# design.net
KiCad netlist of a schematic drawn in Altium Designer
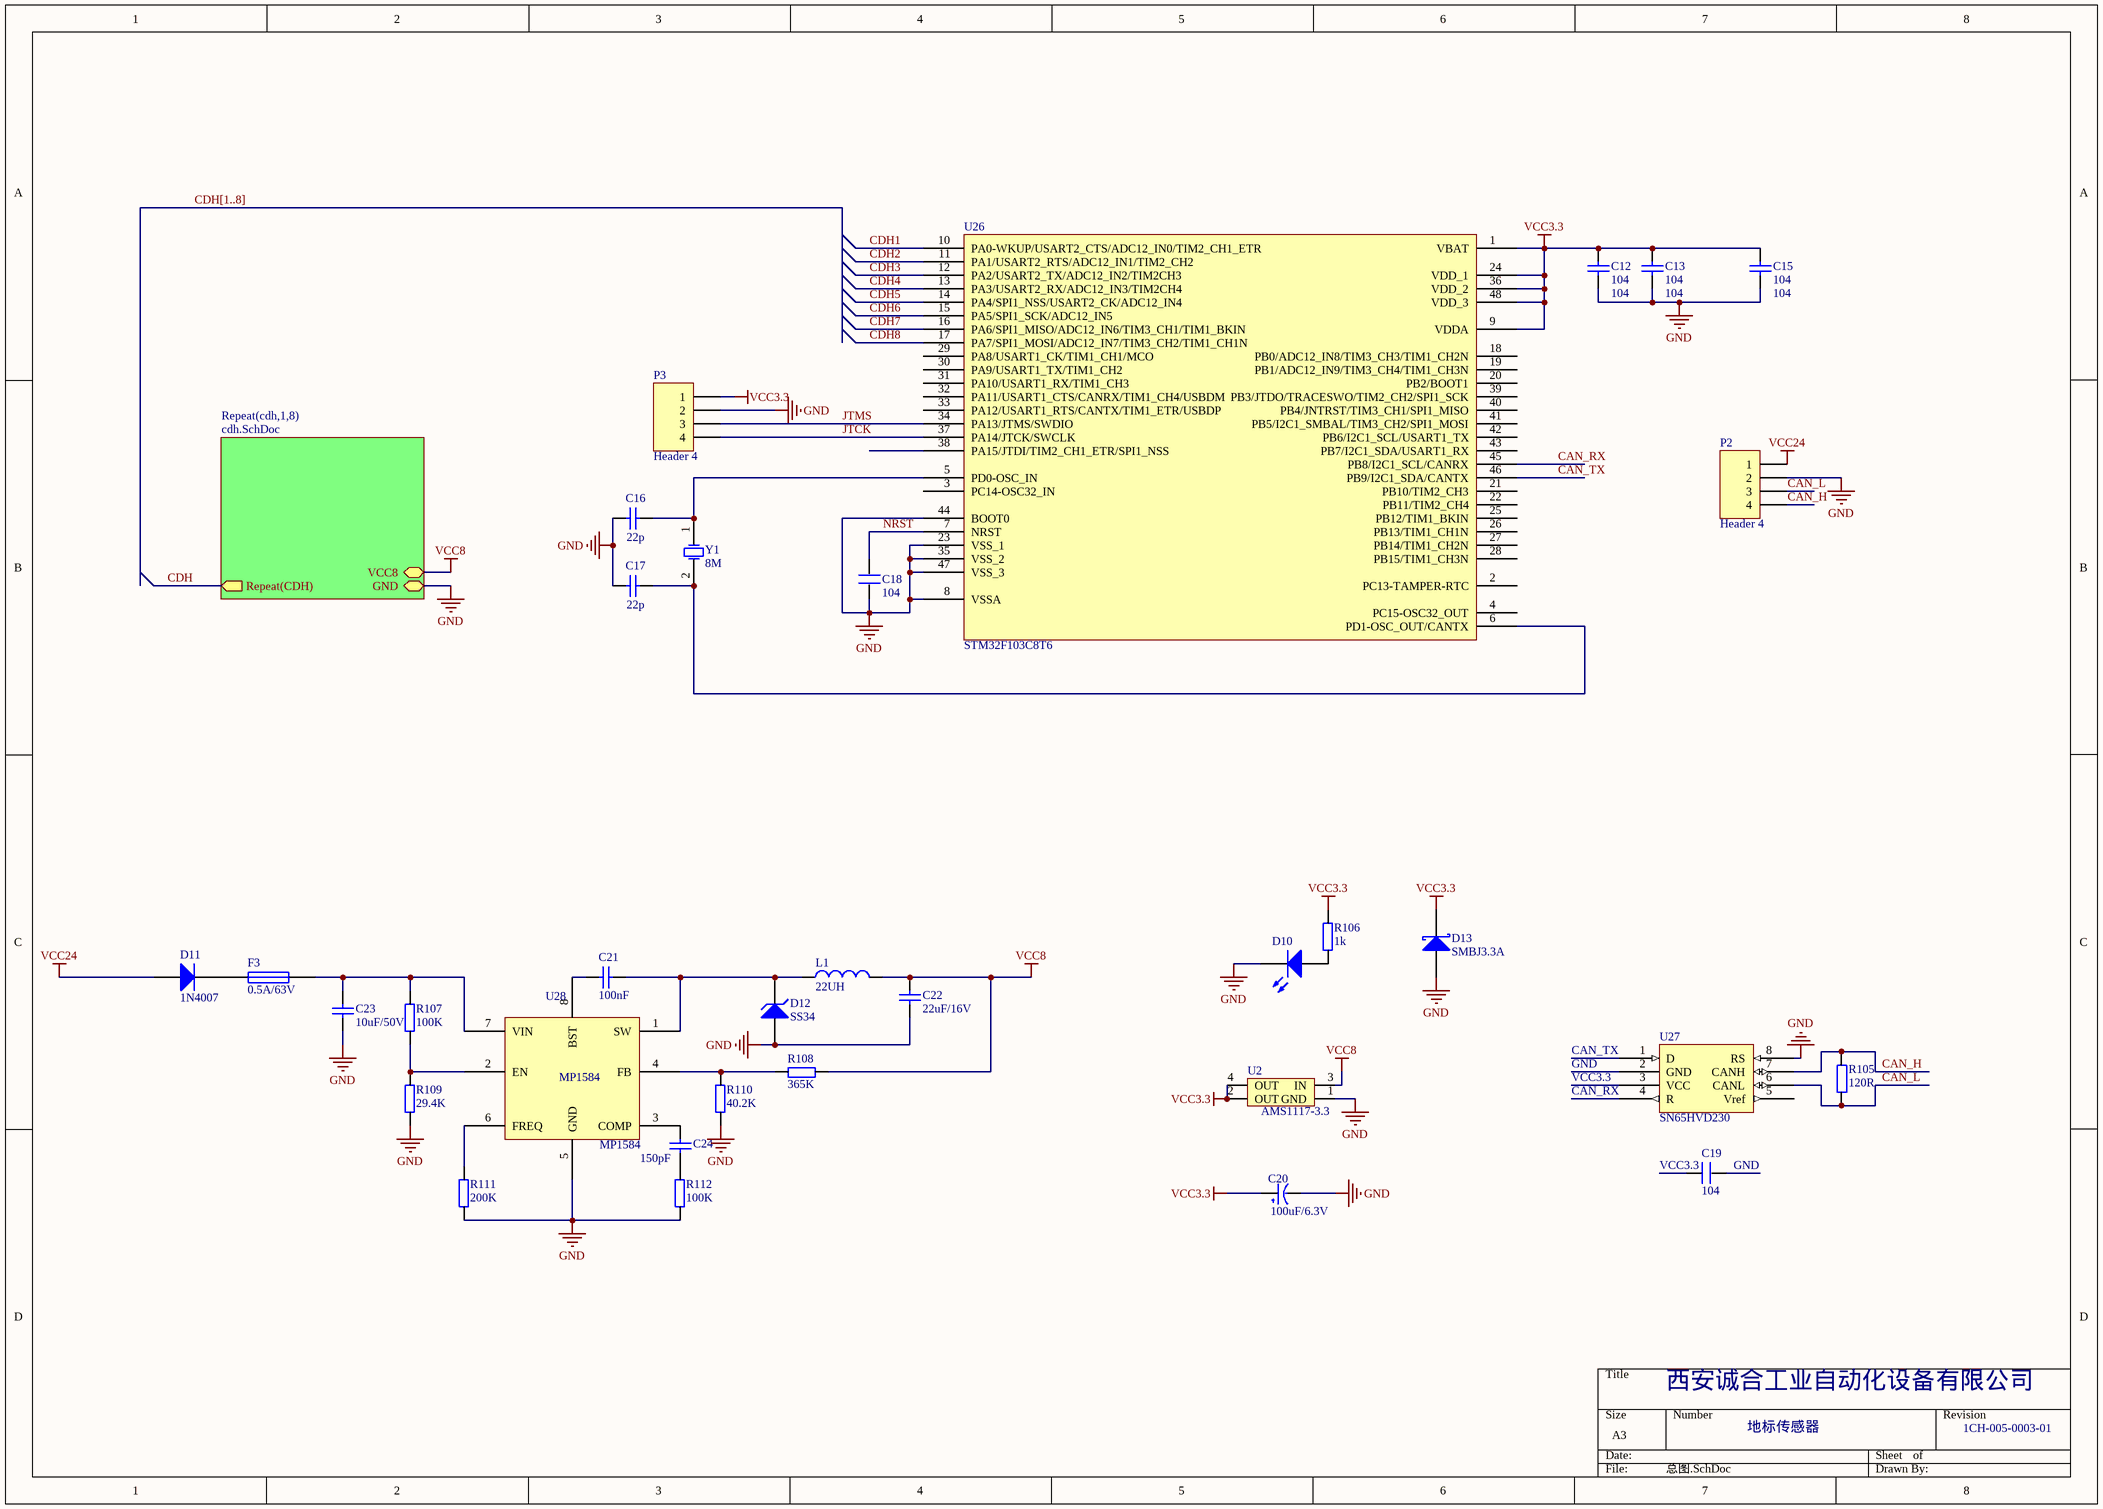
[diagram p0: 总图.SchDoc]

(export (version "E")
  (design (tool "Eeschema 10.0.6"))
  (components
    (comp (ref "C12")
      (value "104")
      (footprint "0603-CAP")
      (description "Capacitor")
      (fields (field (name "ALTIUM_VALUE") "104") (field (name "PUBLISHER") "Altium Limited"))
      (libsource (lib "Miscellaneous Devices") (part "Cap"))
    )
    (comp (ref "C13")
      (value "104")
      (footprint "0603-CAP")
      (description "Capacitor")
      (fields (field (name "ALTIUM_VALUE") "104") (field (name "PUBLISHER") "Altium Limited"))
      (libsource (lib "Miscellaneous Devices") (part "Cap"))
    )
    (comp (ref "C15")
      (value "104")
      (footprint "0603-CAP")
      (description "Capacitor")
      (fields (field (name "ALTIUM_VALUE") "104") (field (name "PUBLISHER") "Altium Limited"))
      (libsource (lib "Miscellaneous Devices") (part "Cap"))
    )
    (comp (ref "C16")
      (value "22p")
      (footprint "0603-CAP")
      (description "Capacitor")
      (fields (field (name "PUBLISHER") "Altium Limited"))
      (libsource (lib "Miscellaneous Devices") (part "Cap"))
    )
    (comp (ref "C17")
      (value "22p")
      (footprint "0603-CAP")
      (description "Capacitor")
      (fields (field (name "PUBLISHER") "Altium Limited"))
      (libsource (lib "Miscellaneous Devices") (part "Cap"))
    )
    (comp (ref "C18")
      (value "104")
      (footprint "0603-CAP")
      (libsource (lib "Explorer STM32F407封装库") (part "C"))
    )
    (comp (ref "C19")
      (value "104")
      (footprint "0603-CAP")
      (libsource (lib "Explorer STM32F407封装库") (part "C_3"))
    )
    (comp (ref "C20") (value "100uF/6.3V") (footprint "3216") (libsource (lib "WarShip V3_SCH") (part "CAP")))
    (comp (ref "C21")
      (value "100nF")
      (footprint "0603-CAP")
      (description "Capacitor (Semiconductor SIM Model)")
      (fields (field (name "Comment") "0.1uF") (field (name "PUBLISHER") "Altium Limited"))
      (libsource (lib "Miscellaneous Devices") (part "Cap Semi"))
    )
    (comp (ref "C22")
      (value "22uF/16V")
      (footprint "1206")
      (description "Capacitor (Semiconductor SIM Model)")
      (fields (field (name "PUBLISHER") "Altium Limited"))
      (libsource (lib "Miscellaneous Devices") (part "Cap Semi"))
    )
    (comp (ref "C23")
      (value "10uF/50V")
      (footprint "1206")
      (description "Capacitor (Semiconductor SIM Model)")
      (fields (field (name "PUBLISHER") "Altium Limited"))
      (libsource (lib "Miscellaneous Devices") (part "Cap Semi"))
    )
    (comp (ref "C24")
      (value "150pF")
      (footprint "0603-CAP")
      (description "Capacitor (Semiconductor SIM Model)")
      (fields (field (name "Comment") "0.1uF") (field (name "PUBLISHER") "Altium Limited"))
      (libsource (lib "Miscellaneous Devices") (part "Cap Semi"))
    )
    (comp (ref "D10")
      (value "LED0")
      (footprint "LC-0805_LED_S1")
      (description "Typical INFRARED GaAs LED")
      (fields (field (name "PUBLISHER") "Altium Limited"))
      (libsource (lib "继电器板_1") (part "LED0"))
    )
    (comp (ref "D11")
      (value "1N4007")
      (footprint "SMA(DO-214AC)_S1")
      (description "Default Diode")
      (fields (field (name "PUBLISHER") "Altium Limited"))
      (libsource (lib "Miscellaneous Devices") (part "Diode"))
    )
    (comp (ref "D12")
      (value "SS34")
      (footprint "SMA(DO-214AC)_S1")
      (description "Zener Diode")
      (fields (field (name "PUBLISHER") "Altium Limited"))
      (libsource (lib "Miscellaneous Devices") (part "D Zener"))
    )
    (comp (ref "D13")
      (value "SMBJ3.3A")
      (footprint "SMB(DO-214AA)_S1")
      (description "Schottky Rectifier")
      (fields (field (name "PUBLISHER") "Altium Limited"))
      (libsource (lib "Miscellaneous Devices") (part "Diode 18TQ045"))
    )
    (comp (ref "F3")
      (value "0.5A/63V")
      (footprint "1206")
      (description "Fuse")
      (fields (field (name "PUBLISHER") "Altium Limited"))
      (libsource (lib "Miscellaneous Devices") (part "Fuse 1"))
    )
    (comp (ref "L1")
      (value "22UH")
      (footprint "L-7*7*4mm-S")
      (description "Inductor")
      (fields (field (name "PUBLISHER") "Altium Limited"))
      (libsource (lib "Miscellaneous Devices") (part "Inductor"))
    )
    (comp (ref "P2")
      (value "Header 4")
      (footprint "DZ-4-3.5")
      (description "Header, 4-Pin")
      (fields (field (name "PUBLISHER") "Altium Limited"))
      (libsource (lib "Miscellaneous Connectors") (part "Header 4"))
    )
    (comp (ref "P3")
      (value "Header 4")
      (footprint "HDR1X4")
      (description "Header, 4-Pin")
      (fields (field (name "PUBLISHER") "Altium Limited"))
      (libsource (lib "Miscellaneous Connectors") (part "Header 4"))
    )
    (comp (ref "R105")
      (value "120R")
      (footprint "0603")
      (libsource (lib "Explorer STM32F407封装库") (part "R_2"))
    )
    (comp (ref "R106") (value "1k") (footprint "0603") (libsource (lib "Explorer STM32F407封装库") (part "R_2")))
    (comp (ref "R107")
      (value "100K")
      (footprint "0603")
      (libsource (lib "Explorer STM32F407封装库") (part "R_2"))
    )
    (comp (ref "R108")
      (value "365K")
      (footprint "0603")
      (libsource (lib "Explorer STM32F407封装库") (part "R_2"))
    )
    (comp (ref "R109")
      (value "29.4K")
      (footprint "0603")
      (libsource (lib "Explorer STM32F407封装库") (part "R_2"))
    )
    (comp (ref "R110")
      (value "40.2K")
      (footprint "0603")
      (libsource (lib "Explorer STM32F407封装库") (part "R_2"))
    )
    (comp (ref "R111")
      (value "200K")
      (footprint "0603")
      (libsource (lib "Explorer STM32F407封装库") (part "R_2"))
    )
    (comp (ref "R112")
      (value "100K")
      (footprint "0603")
      (libsource (lib "Explorer STM32F407封装库") (part "R_2"))
    )
    (comp (ref "U2")
      (value "AMS1117-3.3")
      (footprint "LC-SOT-223")
      (libsource (lib "WarShip V3_SCH") (part "AMS1117"))
    )
    (comp (ref "U26")
      (value "STM32F103C8T6")
      (footprint "LC-LQFP-48")
      (libsource (lib "Schlib1") (part "stm32f103v8t6"))
    )
    (comp (ref "U27")
      (value "SN65HVD230")
      (footprint "SOP-8")
      (libsource (lib "Explorer STM32F407封装库") (part "SN65HVD230D"))
    )
    (comp (ref "U28") (value "MP1584") (footprint "SO-8") (libsource (lib "磁导航") (part "MP1584EN")))
    (comp (ref "Y1")
      (value "8M")
      (footprint "XTAL_US1")
      (description "Crystal Oscillator")
      (fields (field (name "PUBLISHER") "Altium Limited"))
      (libsource (lib "Miscellaneous Devices") (part "XTAL"))
    )
  )
  (nets
    (net (code "1") (name "/CAN_H") (class "Default")
      (node (ref "P2") (pin "4") (pinfunction "4_4") (pintype "passive"))
      (node (ref "R105") (pin "2") (pintype "passive"))
      (node (ref "U27") (pin "7") (pinfunction "CANH_7") (pintype "bidirectional"))
    )
    (net (code "2") (name "/CAN_L") (class "Default")
      (node (ref "P2") (pin "3") (pinfunction "3_3") (pintype "passive"))
      (node (ref "R105") (pin "1") (pintype "passive"))
      (node (ref "U27") (pin "6") (pinfunction "CANL_6") (pintype "bidirectional"))
    )
    (net (code "3") (name "/CAN_RX") (class "Default")
      (node (ref "U26") (pin "45") (pinfunction "PB8/I2C1_SCL/CANRX_45") (pintype "passive"))
      (node (ref "U27") (pin "4") (pinfunction "R_4") (pintype "output"))
    )
    (net (code "4") (name "/CAN_TX") (class "Default")
      (node (ref "U26") (pin "46") (pinfunction "PB9/I2C1_SDA/CANTX_46") (pintype "passive"))
      (node (ref "U27") (pin "1") (pinfunction "D_1") (pintype "input"))
    )
    (net (code "6") (name "/CDH1") (class "Default")
      (node (ref "U26") (pin "10") (pinfunction "PA0-WKUP/USART2_CTS/ADC12_IN0/TIM2_CH1_ETR_10") (pintype "passive"))
    )
    (net (code "7") (name "/CDH2") (class "Default")
      (node (ref "U26") (pin "11") (pinfunction "PA1/USART2_RTS/ADC12_IN1/TIM2_CH2_11") (pintype "passive"))
    )
    (net (code "8") (name "/CDH3") (class "Default")
      (node (ref "U26") (pin "12") (pinfunction "PA2/USART2_TX/ADC12_IN2/TIM2CH3_12") (pintype "passive"))
    )
    (net (code "9") (name "/CDH4") (class "Default")
      (node (ref "U26") (pin "13") (pinfunction "PA3/USART2_RX/ADC12_IN3/TIM2CH4_13") (pintype "passive"))
    )
    (net (code "10") (name "/CDH5") (class "Default")
      (node (ref "U26") (pin "14") (pinfunction "PA4/SPI1_NSS/USART2_CK/ADC12_IN4_14") (pintype "passive"))
    )
    (net (code "11") (name "/CDH6") (class "Default")
      (node (ref "U26") (pin "15") (pinfunction "PA5/SPI1_SCK/ADC12_IN5_15") (pintype "passive"))
    )
    (net (code "12") (name "/CDH7") (class "Default")
      (node (ref "U26") (pin "16") (pinfunction "PA6/SPI1_MISO/ADC12_IN6/TIM3_CH1/TIM1_BKIN_16") (pintype "passive"))
    )
    (net (code "13") (name "/CDH8") (class "Default")
      (node (ref "U26") (pin "17") (pinfunction "PA7/SPI1_MOSI/ADC12_IN7/TIM3_CH2/TIM1_CH1N_17") (pintype "passive"))
    )
    (net (code "15") (name "/JTCK") (class "Default")
      (node (ref "P3") (pin "4") (pinfunction "4_4") (pintype "passive"))
      (node (ref "U26") (pin "37") (pinfunction "PA14/JTCK/SWCLK_37") (pintype "passive"))
    )
    (net (code "16") (name "/JTMS") (class "Default")
      (node (ref "P3") (pin "3") (pinfunction "3_3") (pintype "passive"))
      (node (ref "U26") (pin "34") (pinfunction "PA13/JTMS/SWDIO_34") (pintype "passive"))
    )
    (net (code "17") (name "/NRST") (class "Default")
      (node (ref "C18") (pin "2") (pintype "passive"))
      (node (ref "U26") (pin "7") (pinfunction "NRST_7") (pintype "passive"))
    )
    (net (code "18") (name "GND") (class "Default")
      (node (ref "C12") (pin "2") (pinfunction "2_2") (pintype "passive"))
      (node (ref "C13") (pin "2") (pinfunction "2_2") (pintype "passive"))
      (node (ref "C15") (pin "2") (pinfunction "2_2") (pintype "passive"))
      (node (ref "C16") (pin "2") (pinfunction "2_2") (pintype "passive"))
      (node (ref "C17") (pin "2") (pinfunction "2_2") (pintype "passive"))
      (node (ref "C18") (pin "1") (pintype "passive"))
      (node (ref "C19") (pin "2") (pintype "passive"))
      (node (ref "C20") (pin "2") (pinfunction "GND_2") (pintype "passive"))
      (node (ref "C22") (pin "1") (pinfunction "1_1") (pintype "passive"))
      (node (ref "C23") (pin "2") (pinfunction "2_2") (pintype "passive"))
      (node (ref "D10") (pin "K") (pinfunction "K_K") (pintype "passive"))
      (node (ref "D12") (pin "1") (pinfunction "A_1") (pintype "passive"))
      (node (ref "D13") (pin "2") (pinfunction "A_2") (pintype "passive"))
      (node (ref "P2") (pin "2") (pinfunction "2_2") (pintype "passive"))
      (node (ref "P3") (pin "2") (pinfunction "2_2") (pintype "passive"))
      (node (ref "R109") (pin "2") (pintype "passive"))
      (node (ref "R110") (pin "2") (pintype "passive"))
      (node (ref "R111") (pin "2") (pintype "passive"))
      (node (ref "R112") (pin "2") (pintype "passive"))
      (node (ref "U2") (pin "1") (pinfunction "GND_1") (pintype "passive"))
      (node (ref "U26") (pin "23") (pinfunction "VSS_1_23") (pintype "passive"))
      (node (ref "U26") (pin "35") (pinfunction "VSS_2_35") (pintype "passive"))
      (node (ref "U26") (pin "44") (pinfunction "BOOT0_44") (pintype "passive"))
      (node (ref "U26") (pin "47") (pinfunction "VSS_3_47") (pintype "passive"))
      (node (ref "U26") (pin "8") (pinfunction "VSSA_8") (pintype "passive"))
      (node (ref "U27") (pin "2") (pinfunction "GND_2") (pintype "power_in"))
      (node (ref "U27") (pin "8") (pinfunction "RS_8") (pintype "input"))
      (node (ref "U28") (pin "5") (pinfunction "GND_5") (pintype "passive"))
    )
    (net (code "19") (name "Net-(C24-Pad1)") (class "Default")
      (node (ref "C24") (pin "1") (pinfunction "1_1") (pintype "passive"))
      (node (ref "R112") (pin "1") (pintype "passive"))
    )
    (net (code "20") (name "Net-(D10-PadA)") (class "Default")
      (node (ref "D10") (pin "A") (pinfunction "A_A") (pintype "passive"))
      (node (ref "R106") (pin "2") (pintype "passive"))
    )
    (net (code "21") (name "Net-(D11-K)") (class "Default")
      (node (ref "D11") (pin "2") (pinfunction "K_2") (pintype "passive"))
      (node (ref "F3") (pin "1") (pinfunction "1_1") (pintype "passive"))
    )
    (net (code "22") (name "Net-(D12-K)") (class "Default")
      (node (ref "C21") (pin "1") (pinfunction "1_1") (pintype "passive"))
      (node (ref "D12") (pin "2") (pinfunction "K_2") (pintype "passive"))
      (node (ref "L1") (pin "1") (pinfunction "1_1") (pintype "passive"))
      (node (ref "U28") (pin "1") (pinfunction "SW_1") (pintype "passive"))
    )
    (net (code "23") (name "Net-(U26-PD0-OSC_IN)") (class "Default")
      (node (ref "C16") (pin "1") (pinfunction "1_1") (pintype "passive"))
      (node (ref "U26") (pin "5") (pinfunction "PD0-OSC_IN_5") (pintype "passive"))
      (node (ref "Y1") (pin "1") (pinfunction "OSC1_1") (pintype "passive"))
    )
    (net (code "24") (name "Net-(U26-PD1-OSC_OUT{slash}CANTX)") (class "Default")
      (node (ref "C17") (pin "1") (pinfunction "1_1") (pintype "passive"))
      (node (ref "U26") (pin "6") (pinfunction "PD1-OSC_OUT/CANTX_6") (pintype "passive"))
      (node (ref "Y1") (pin "2") (pinfunction "OSC2_2") (pintype "passive"))
    )
    (net (code "25") (name "Net-(U28-BST)") (class "Default")
      (node (ref "C21") (pin "2") (pinfunction "2_2") (pintype "passive"))
      (node (ref "U28") (pin "8") (pinfunction "BST_8") (pintype "passive"))
    )
    (net (code "26") (name "Net-(U28-COMP)") (class "Default")
      (node (ref "C24") (pin "2") (pinfunction "2_2") (pintype "passive"))
      (node (ref "U28") (pin "3") (pinfunction "COMP_3") (pintype "passive"))
    )
    (net (code "27") (name "Net-(U28-EN)") (class "Default")
      (node (ref "R107") (pin "2") (pintype "passive"))
      (node (ref "R109") (pin "1") (pintype "passive"))
      (node (ref "U28") (pin "2") (pinfunction "EN_2") (pintype "passive"))
    )
    (net (code "28") (name "Net-(U28-FB)") (class "Default")
      (node (ref "R108") (pin "1") (pintype "passive"))
      (node (ref "R110") (pin "1") (pintype "passive"))
      (node (ref "U28") (pin "4") (pinfunction "FB_4") (pintype "passive"))
    )
    (net (code "29") (name "Net-(U28-FREQ)") (class "Default")
      (node (ref "R111") (pin "1") (pintype "passive"))
      (node (ref "U28") (pin "6") (pinfunction "FREQ_6") (pintype "passive"))
    )
    (net (code "30") (name "Net-(U28-VIN)") (class "Default")
      (node (ref "C23") (pin "1") (pinfunction "1_1") (pintype "passive"))
      (node (ref "F3") (pin "2") (pinfunction "2_2") (pintype "passive"))
      (node (ref "R107") (pin "1") (pintype "passive"))
      (node (ref "U28") (pin "7") (pinfunction "VIN_7") (pintype "passive"))
    )
    (net (code "31") (name "VCC3.3") (class "Default")
      (node (ref "C12") (pin "1") (pinfunction "1_1") (pintype "passive"))
      (node (ref "C13") (pin "1") (pinfunction "1_1") (pintype "passive"))
      (node (ref "C15") (pin "1") (pinfunction "1_1") (pintype "passive"))
      (node (ref "C19") (pin "1") (pintype "passive"))
      (node (ref "C20") (pin "1") (pinfunction "VCC_1") (pintype "passive"))
      (node (ref "D13") (pin "1") (pinfunction "K_1") (pintype "passive"))
      (node (ref "P3") (pin "1") (pinfunction "1_1") (pintype "passive"))
      (node (ref "R106") (pin "1") (pintype "passive"))
      (node (ref "U2") (pin "2") (pinfunction "OUT_2") (pintype "passive"))
      (node (ref "U2") (pin "4") (pinfunction "OUT_4") (pintype "passive"))
      (node (ref "U26") (pin "1") (pinfunction "VBAT_1") (pintype "passive"))
      (node (ref "U26") (pin "24") (pinfunction "VDD_1_24") (pintype "passive"))
      (node (ref "U26") (pin "36") (pinfunction "VDD_2_36") (pintype "passive"))
      (node (ref "U26") (pin "48") (pinfunction "VDD_3_48") (pintype "passive"))
      (node (ref "U26") (pin "9") (pinfunction "VDDA_9") (pintype "passive"))
      (node (ref "U27") (pin "3") (pinfunction "VCC_3") (pintype "power_in"))
    )
    (net (code "32") (name "VCC8") (class "Default")
      (node (ref "C22") (pin "2") (pinfunction "2_2") (pintype "passive"))
      (node (ref "L1") (pin "2") (pinfunction "2_2") (pintype "passive"))
      (node (ref "R108") (pin "2") (pintype "passive"))
      (node (ref "U2") (pin "3") (pinfunction "IN_3") (pintype "passive"))
    )
    (net (code "33") (name "VCC24") (class "Default")
      (node (ref "D11") (pin "1") (pinfunction "A_1") (pintype "passive"))
      (node (ref "P2") (pin "1") (pinfunction "1_1") (pintype "passive"))
    )
    (net (code "34") (name "unconnected-(U26-PA8{slash}USART1_CK{slash}TIM1_CH1{slash}MCO-Pad29)") (class "Default")
      (node (ref "U26") (pin "29") (pinfunction "PA8/USART1_CK/TIM1_CH1/MCO_29") (pintype "passive"))
    )
    (net (code "35") (name "unconnected-(U26-PA9{slash}USART1_TX{slash}TIM1_CH2-Pad30)") (class "Default")
      (node (ref "U26") (pin "30") (pinfunction "PA9/USART1_TX/TIM1_CH2_30") (pintype "passive"))
    )
    (net (code "36") (name "unconnected-(U26-PA10{slash}USART1_RX{slash}TIM1_CH3-Pad31)") (class "Default")
      (node (ref "U26") (pin "31") (pinfunction "PA10/USART1_RX/TIM1_CH3_31") (pintype "passive"))
    )
    (net (code "37") (name "unconnected-(U26-PA11{slash}USART1_CTS{slash}CANRX{slash}TIM1_CH4{slash}USBDM-Pad32)") (class "Default")
      (node (ref "U26") (pin "32") (pinfunction "PA11/USART1_CTS/CANRX/TIM1_CH4/USBDM_32") (pintype "passive"))
    )
    (net (code "38") (name "unconnected-(U26-PA12{slash}USART1_RTS{slash}CANTX{slash}TIM1_ETR{slash}USBDP-Pad33)") (class "Default")
      (node (ref "U26") (pin "33") (pinfunction "PA12/USART1_RTS/CANTX/TIM1_ETR/USBDP_33") (pintype "passive"))
    )
    (net (code "39") (name "unconnected-(U26-PA15{slash}JTDI{slash}TIM2_CH1_ETR{slash}SPI1_NSS-Pad38)") (class "Default")
      (node (ref "U26") (pin "38") (pinfunction "PA15/JTDI/TIM2_CH1_ETR/SPI1_NSS_38") (pintype "passive"))
    )
    (net (code "40") (name "unconnected-(U26-PB0{slash}ADC12_IN8{slash}TIM3_CH3{slash}TIM1_CH2N-Pad18)") (class "Default")
      (node (ref "U26") (pin "18") (pinfunction "PB0/ADC12_IN8/TIM3_CH3/TIM1_CH2N_18") (pintype "passive"))
    )
    (net (code "41") (name "unconnected-(U26-PB1{slash}ADC12_IN9{slash}TIM3_CH4{slash}TIM1_CH3N-Pad19)") (class "Default")
      (node (ref "U26") (pin "19") (pinfunction "PB1/ADC12_IN9/TIM3_CH4/TIM1_CH3N_19") (pintype "passive"))
    )
    (net (code "42") (name "unconnected-(U26-PB2{slash}BOOT1-Pad20)") (class "Default")
      (node (ref "U26") (pin "20") (pinfunction "PB2/BOOT1_20") (pintype "passive"))
    )
    (net (code "43") (name "unconnected-(U26-PB3{slash}JTDO{slash}TRACESWO{slash}TIM2_CH2{slash}SPI1_SCK-Pad39)") (class "Default")
      (node (ref "U26") (pin "39") (pinfunction "PB3/JTDO/TRACESWO/TIM2_CH2/SPI1_SCK_39") (pintype "passive"))
    )
    (net (code "44") (name "unconnected-(U26-PB4{slash}JNTRST{slash}TIM3_CH1{slash}SPI1_MISO-Pad40)") (class "Default")
      (node (ref "U26") (pin "40") (pinfunction "PB4/JNTRST/TIM3_CH1/SPI1_MISO_40") (pintype "passive"))
    )
    (net (code "45") (name "unconnected-(U26-PB5{slash}I2C1_SMBAL{slash}TIM3_CH2{slash}SPI1_MOSI-Pad41)") (class "Default")
      (node (ref "U26") (pin "41") (pinfunction "PB5/I2C1_SMBAL/TIM3_CH2/SPI1_MOSI_41") (pintype "passive"))
    )
    (net (code "46") (name "unconnected-(U26-PB6{slash}I2C1_SCL{slash}USART1_TX-Pad42)") (class "Default")
      (node (ref "U26") (pin "42") (pinfunction "PB6/I2C1_SCL/USART1_TX_42") (pintype "passive"))
    )
    (net (code "47") (name "unconnected-(U26-PB7{slash}I2C1_SDA{slash}USART1_RX-Pad43)") (class "Default")
      (node (ref "U26") (pin "43") (pinfunction "PB7/I2C1_SDA/USART1_RX_43") (pintype "passive"))
    )
    (net (code "48") (name "unconnected-(U26-PB10{slash}TIM2_CH3-Pad21)") (class "Default")
      (node (ref "U26") (pin "21") (pinfunction "PB10/TIM2_CH3_21") (pintype "passive"))
    )
    (net (code "49") (name "unconnected-(U26-PB11{slash}TIM2_CH4-Pad22)") (class "Default")
      (node (ref "U26") (pin "22") (pinfunction "PB11/TIM2_CH4_22") (pintype "passive"))
    )
    (net (code "50") (name "unconnected-(U26-PB12{slash}TIM1_BKIN-Pad25)") (class "Default")
      (node (ref "U26") (pin "25") (pinfunction "PB12/TIM1_BKIN_25") (pintype "passive"))
    )
    (net (code "51") (name "unconnected-(U26-PB13{slash}TIM1_CH1N-Pad26)") (class "Default")
      (node (ref "U26") (pin "26") (pinfunction "PB13/TIM1_CH1N_26") (pintype "passive"))
    )
    (net (code "52") (name "unconnected-(U26-PB14{slash}TIM1_CH2N-Pad27)") (class "Default")
      (node (ref "U26") (pin "27") (pinfunction "PB14/TIM1_CH2N_27") (pintype "passive"))
    )
    (net (code "53") (name "unconnected-(U26-PB15{slash}TIM1_CH3N-Pad28)") (class "Default")
      (node (ref "U26") (pin "28") (pinfunction "PB15/TIM1_CH3N_28") (pintype "passive"))
    )
    (net (code "54") (name "unconnected-(U26-PC13-TAMPER-RTC-Pad2)") (class "Default")
      (node (ref "U26") (pin "2") (pinfunction "PC13-TAMPER-RTC_2") (pintype "passive"))
    )
    (net (code "55") (name "unconnected-(U26-PC14-OSC32_IN-Pad3)") (class "Default")
      (node (ref "U26") (pin "3") (pinfunction "PC14-OSC32_IN_3") (pintype "passive"))
    )
    (net (code "56") (name "unconnected-(U26-PC15-OSC32_OUT-Pad4)") (class "Default")
      (node (ref "U26") (pin "4") (pinfunction "PC15-OSC32_OUT_4") (pintype "passive"))
    )
    (net (code "57") (name "unconnected-(U27-Vref-Pad5)") (class "Default")
      (node (ref "U27") (pin "5") (pinfunction "Vref_5") (pintype "output"))
    )
  )
)
